# AUDIO.net
KiCad netlist of a schematic drawn in Altium Designer
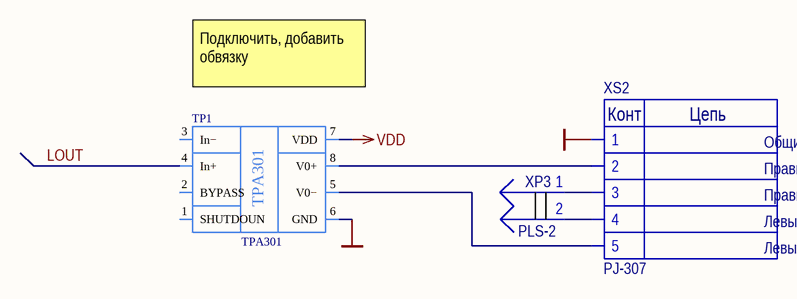
[diagram p0: AUDIO.SchDoc]

(export (version "E")
  (design (tool "Eeschema 10.0.6"))
  (components
    (comp (ref "TP1")
      (value "TPA301")
      (footprint "TPA301 TSOP65P490X110_HS-9L")
      (libsource (lib "Schlib1") (part "TPA301"))
    )
    (comp (ref "XP3") (value "PLS-2") (footprint "PLS-2") (libsource (lib "7.Connectors") (part "PLS-2")))
    (comp (ref "XS2") (value "PJ-307") (footprint "PJ-307") (libsource (lib "7. Connectors") (part "PJ-307")))
  )
  (nets
    (net (code "1") (name "/LOUT") (class "Default")
      (node (ref "TP1") (pin "4") (pinfunction "In+_4") (pintype "passive"))
    )
    (net (code "2") (name "GND") (class "Default")
      (node (ref "TP1") (pin "6") (pinfunction "GND_6") (pintype "passive"))
      (node (ref "XS2") (pin "1") (pinfunction "1_1") (pintype "passive"))
    )
    (net (code "3") (name "Net-(TP1-V0+)") (class "Default")
      (node (ref "TP1") (pin "8") (pinfunction "V0+_8") (pintype "passive"))
      (node (ref "XS2") (pin "2") (pinfunction "2_2") (pintype "passive"))
    )
    (net (code "4") (name "Net-(TP1-V0−)") (class "Default")
      (node (ref "TP1") (pin "5") (pinfunction "V0−_5") (pintype "passive"))
      (node (ref "XS2") (pin "5") (pinfunction "5_5") (pintype "passive"))
    )
    (net (code "5") (name "Net-(XP3-Pad1)") (class "Default")
      (node (ref "XP3") (pin "1") (pinfunction "1_1") (pintype "passive"))
      (node (ref "XS2") (pin "3") (pinfunction "3_3") (pintype "passive"))
    )
    (net (code "6") (name "Net-(XP3-Pad2)") (class "Default")
      (node (ref "XP3") (pin "2") (pinfunction "2_2") (pintype "passive"))
      (node (ref "XS2") (pin "4") (pinfunction "4_4") (pintype "passive"))
    )
    (net (code "7") (name "VDD") (class "Default")
      (node (ref "TP1") (pin "7") (pinfunction "VDD_7") (pintype "passive"))
    )
    (net (code "8") (name "unconnected-(TP1-BYPASS-Pad2)") (class "Default")
      (node (ref "TP1") (pin "2") (pinfunction "BYPASS_2") (pintype "passive"))
    )
    (net (code "9") (name "unconnected-(TP1-In−-Pad3)") (class "Default")
      (node (ref "TP1") (pin "3") (pinfunction "In−_3") (pintype "passive"))
    )
    (net (code "10") (name "unconnected-(TP1-SHUTDOUN-Pad1)") (class "Default")
      (node (ref "TP1") (pin "1") (pinfunction "SHUTDOUN_1") (pintype "passive"))
    )
  )
)
